# cw312_xc7a35t_fpga_cfg.net
KiCad netlist of a schematic drawn in Altium Designer
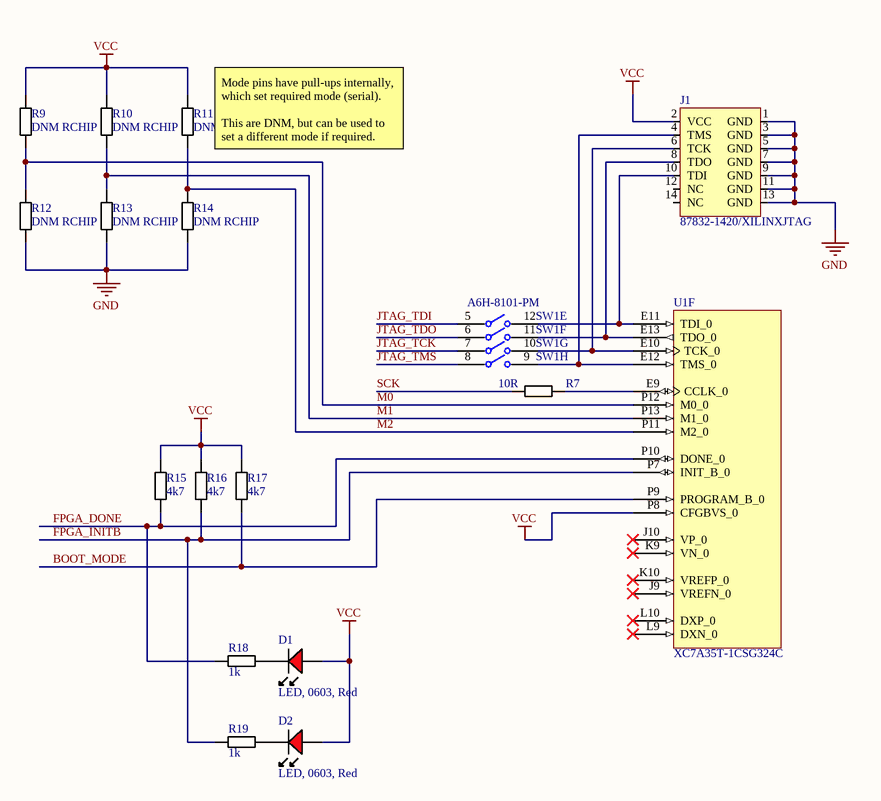
[diagram p0: cw312_xc7a35t_fpga_cfg.SchDoc]

(export (version "E")
  (design (tool "Eeschema 10.0.6"))
  (components
    (comp (ref "D1")
      (value "LED, 0603, Red")
      (footprint "LED-0603-RED")
      (description "Chip LED, Red")
      (fields (field (name "PART NUMBER") "LEDCHIP_0603_RED"))
      (libsource (lib "NewAE_AltiumLib") (part "LED_RED"))
    )
    (comp (ref "D2")
      (value "LED, 0603, Red")
      (footprint "LED-0603-RED")
      (description "Chip LED, Red")
      (fields (field (name "PART NUMBER") "LEDCHIP_0603_RED"))
      (libsource (lib "NewAE_AltiumLib") (part "LED_RED"))
    )
    (comp (ref "J1")
      (value "87832-1420/XILINXJTAG")
      (footprint "87832-1420")
      (description "Molex 14-pin SMD, JTAG Pinout")
      (fields (field (name "MANUFACTURE 1 PART NUMBER") "87832-1420"))
      (libsource (lib "CW1200_MainBoard") (part "87832-1420/XILINXJTAG"))
    )
    (comp (ref "R7")
      (value "10R")
      (footprint "RESC1608X55N")
      (description "10R res, 0603, 1%, 1/10W")
      (fields (field (name "PART NUMBER") "RCHIP-10R-0603") (field (name "TOLERANCE") "1%"))
      (libsource (lib "") (part "RES-EU_1"))
    )
    (comp (ref "R9")
      (value "DNM RCHIP")
      (footprint "RESC1608X55N")
      (description "Do Not Mount Resistor")
      (fields (field (name "PART NUMBER") "RCHIP-DNM-0603"))
      (libsource (lib "") (part "RES-EU_2"))
    )
    (comp (ref "R10")
      (value "DNM RCHIP")
      (footprint "RESC1608X55N")
      (description "Do Not Mount Resistor")
      (fields (field (name "PART NUMBER") "RCHIP-DNM-0603"))
      (libsource (lib "") (part "RES-EU_2"))
    )
    (comp (ref "R11")
      (value "DNM RCHIP")
      (footprint "RESC1608X55N")
      (description "Do Not Mount Resistor")
      (fields (field (name "PART NUMBER") "RCHIP-DNM-0603"))
      (libsource (lib "") (part "RES-EU_2"))
    )
    (comp (ref "R12")
      (value "DNM RCHIP")
      (footprint "RESC1608X55N")
      (description "Do Not Mount Resistor")
      (fields (field (name "PART NUMBER") "RCHIP-DNM-0603"))
      (libsource (lib "") (part "RES-EU_2"))
    )
    (comp (ref "R13")
      (value "DNM RCHIP")
      (footprint "RESC1608X55N")
      (description "Do Not Mount Resistor")
      (fields (field (name "PART NUMBER") "RCHIP-DNM-0603"))
      (libsource (lib "") (part "RES-EU_2"))
    )
    (comp (ref "R14")
      (value "DNM RCHIP")
      (footprint "RESC1608X55N")
      (description "Do Not Mount Resistor")
      (fields (field (name "PART NUMBER") "RCHIP-DNM-0603"))
      (libsource (lib "") (part "RES-EU_2"))
    )
    (comp (ref "R15")
      (value "4k7")
      (footprint "RESC1608X55N")
      (description "4k7 res, 0603, 1%, 1/10W")
      (fields (field (name "PART NUMBER") "RCHIP-4K7-0603") (field (name "TOLERANCE") "1%"))
      (libsource (lib "NewAE_AltiumLib") (part "RES-EU"))
    )
    (comp (ref "R16")
      (value "4k7")
      (footprint "RESC1608X55N")
      (description "4k7 res, 0603, 1%, 1/10W")
      (fields (field (name "PART NUMBER") "RCHIP-4K7-0603") (field (name "TOLERANCE") "1%"))
      (libsource (lib "NewAE_AltiumLib") (part "RES-EU"))
    )
    (comp (ref "R17")
      (value "4k7")
      (footprint "RESC1608X55N")
      (description "4k7 res, 0603, 1%, 1/10W")
      (fields (field (name "PART NUMBER") "RCHIP-4K7-0603") (field (name "TOLERANCE") "1%"))
      (libsource (lib "NewAE_AltiumLib") (part "RES-EU"))
    )
    (comp (ref "R18")
      (value "1k")
      (footprint "RESC1608X55N")
      (description "1k res, 0603, 1%, 1/10W")
      (fields (field (name "PART NUMBER") "RCHIP-1K-0603") (field (name "TOLERANCE") "1%"))
      (libsource (lib "") (part "RES-EU_1"))
    )
    (comp (ref "R19")
      (value "1k")
      (footprint "RESC1608X55N")
      (description "1k res, 0603, 1%, 1/10W")
      (fields (field (name "PART NUMBER") "RCHIP-1K-0603") (field (name "TOLERANCE") "1%"))
      (libsource (lib "") (part "RES-EU_1"))
    )
    (comp (ref "SW1")
      (value "A6H-8101-PM")
      (footprint "FP-A6H-8101-PM-MFG")
      (description "SWITCH SLIDE DIP SPST 25MA 24V")
      (libsource (lib "Altium Content Vault") (part "b1c630a2f26d6f55c46b66680387f8a"))
    )
    (comp (ref "U1")
      (value "XC7A35T-1CSG324C")
      (footprint "CSG324")
      (description "Artix-7 FPGA, 210 User I/Os, 0 GTP, 324-Ball BGA, Speed Grade 1, Commercial Grade, Pb-Free")
      (fields (field (name "MANUFACTURER") "Xilinx"))
      (libsource (lib "Altium Content Vault") (part "XLNX-XC7A35T-CSG324"))
    )
  )
  (nets
    (net (code "1") (name "/BOOT_MODE") (class "Default")
      (node (ref "R17") (pin "2") (pinfunction "2_2") (pintype "passive"))
      (node (ref "U1") (pin "P9") (pinfunction "PROGRAM_B_0_P9") (pintype "input"))
    )
    (net (code "2") (name "/FPGA_DONE") (class "Default")
      (node (ref "R15") (pin "2") (pinfunction "2_2") (pintype "passive"))
      (node (ref "R18") (pin "1") (pinfunction "1_1") (pintype "passive"))
      (node (ref "U1") (pin "P10") (pinfunction "DONE_0_P10") (pintype "bidirectional"))
    )
    (net (code "3") (name "/FPGA_INITB") (class "Default")
      (node (ref "R16") (pin "2") (pinfunction "2_2") (pintype "passive"))
      (node (ref "R19") (pin "1") (pinfunction "1_1") (pintype "passive"))
      (node (ref "U1") (pin "P7") (pinfunction "INIT_B_0_P7") (pintype "bidirectional"))
    )
    (net (code "4") (name "/JTAG_TCK") (class "Default")
      (node (ref "SW1") (pin "7") (pinfunction "7_7") (pintype "passive"))
    )
    (net (code "5") (name "/JTAG_TDI") (class "Default")
      (node (ref "SW1") (pin "5") (pinfunction "5_5") (pintype "passive"))
    )
    (net (code "6") (name "/JTAG_TDO") (class "Default")
      (node (ref "SW1") (pin "6") (pinfunction "6_6") (pintype "passive"))
    )
    (net (code "7") (name "/JTAG_TMS") (class "Default")
      (node (ref "SW1") (pin "8") (pinfunction "8_8") (pintype "passive"))
    )
    (net (code "8") (name "/M0") (class "Default")
      (node (ref "R12") (pin "2") (pinfunction "2_2") (pintype "passive"))
      (node (ref "R9") (pin "1") (pinfunction "1_1") (pintype "passive"))
      (node (ref "U1") (pin "P12") (pinfunction "M0_0_P12") (pintype "input"))
    )
    (net (code "9") (name "/M1") (class "Default")
      (node (ref "R10") (pin "1") (pinfunction "1_1") (pintype "passive"))
      (node (ref "R13") (pin "2") (pinfunction "2_2") (pintype "passive"))
      (node (ref "U1") (pin "P13") (pinfunction "M1_0_P13") (pintype "input"))
    )
    (net (code "10") (name "/M2") (class "Default")
      (node (ref "R11") (pin "1") (pinfunction "1_1") (pintype "passive"))
      (node (ref "R14") (pin "2") (pinfunction "2_2") (pintype "passive"))
      (node (ref "U1") (pin "P11") (pinfunction "M2_0_P11") (pintype "input"))
    )
    (net (code "11") (name "/SCK") (class "Default")
      (node (ref "R7") (pin "1") (pinfunction "1_1") (pintype "passive"))
    )
    (net (code "12") (name "GND") (class "Default")
      (node (ref "J1") (pin "1") (pinfunction "GND_1") (pintype "passive"))
      (node (ref "J1") (pin "11") (pinfunction "GND_11") (pintype "passive"))
      (node (ref "J1") (pin "13") (pinfunction "GND_13") (pintype "passive"))
      (node (ref "J1") (pin "3") (pinfunction "GND_3") (pintype "passive"))
      (node (ref "J1") (pin "5") (pinfunction "GND_5") (pintype "passive"))
      (node (ref "J1") (pin "7") (pinfunction "GND_7") (pintype "passive"))
      (node (ref "J1") (pin "9") (pinfunction "GND_9") (pintype "passive"))
      (node (ref "R12") (pin "1") (pinfunction "1_1") (pintype "passive"))
      (node (ref "R13") (pin "1") (pinfunction "1_1") (pintype "passive"))
      (node (ref "R14") (pin "1") (pinfunction "1_1") (pintype "passive"))
    )
    (net (code "13") (name "Net-(D1-PadK)") (class "Default")
      (node (ref "D1") (pin "K") (pinfunction "K_K") (pintype "passive"))
      (node (ref "R18") (pin "2") (pinfunction "2_2") (pintype "passive"))
    )
    (net (code "14") (name "Net-(D2-PadK)") (class "Default")
      (node (ref "D2") (pin "K") (pinfunction "K_K") (pintype "passive"))
      (node (ref "R19") (pin "2") (pinfunction "2_2") (pintype "passive"))
    )
    (net (code "15") (name "Net-(J1-TCK)") (class "Default")
      (node (ref "J1") (pin "6") (pinfunction "TCK_6") (pintype "passive"))
      (node (ref "SW1") (pin "10") (pinfunction "10_10") (pintype "passive"))
      (node (ref "U1") (pin "E10") (pinfunction "TCK_0_E10") (pintype "input"))
    )
    (net (code "16") (name "Net-(J1-TDI)") (class "Default")
      (node (ref "J1") (pin "10") (pinfunction "TDI_10") (pintype "passive"))
      (node (ref "SW1") (pin "12") (pinfunction "12_12") (pintype "passive"))
      (node (ref "U1") (pin "E11") (pinfunction "TDI_0_E11") (pintype "input"))
    )
    (net (code "17") (name "Net-(J1-TDO)") (class "Default")
      (node (ref "J1") (pin "8") (pinfunction "TDO_8") (pintype "passive"))
      (node (ref "SW1") (pin "11") (pinfunction "11_11") (pintype "passive"))
      (node (ref "U1") (pin "E13") (pinfunction "TDO_0_E13") (pintype "output"))
    )
    (net (code "18") (name "Net-(J1-TMS)") (class "Default")
      (node (ref "J1") (pin "4") (pinfunction "TMS_4") (pintype "passive"))
      (node (ref "SW1") (pin "9") (pinfunction "9_9") (pintype "passive"))
      (node (ref "U1") (pin "E12") (pinfunction "TMS_0_E12") (pintype "input"))
    )
    (net (code "19") (name "Net-(U1F-CCLK_0)") (class "Default")
      (node (ref "R7") (pin "2") (pinfunction "2_2") (pintype "passive"))
      (node (ref "U1") (pin "E9") (pinfunction "CCLK_0_E9") (pintype "bidirectional"))
    )
    (net (code "20") (name "VCC") (class "Default")
      (node (ref "D1") (pin "A") (pinfunction "A_A") (pintype "passive"))
      (node (ref "D2") (pin "A") (pinfunction "A_A") (pintype "passive"))
      (node (ref "J1") (pin "2") (pinfunction "VCC_2") (pintype "passive"))
      (node (ref "R10") (pin "2") (pinfunction "2_2") (pintype "passive"))
      (node (ref "R11") (pin "2") (pinfunction "2_2") (pintype "passive"))
      (node (ref "R15") (pin "1") (pinfunction "1_1") (pintype "passive"))
      (node (ref "R16") (pin "1") (pinfunction "1_1") (pintype "passive"))
      (node (ref "R17") (pin "1") (pinfunction "1_1") (pintype "passive"))
      (node (ref "R9") (pin "2") (pinfunction "2_2") (pintype "passive"))
      (node (ref "U1") (pin "P8") (pinfunction "CFGBVS_0_P8") (pintype "input"))
    )
    (net (code "21") (name "unconnected-(J1-NC-Pad12)") (class "Default")
      (node (ref "J1") (pin "12") (pinfunction "NC_12") (pintype "passive"))
    )
    (net (code "22") (name "unconnected-(J1-NC-Pad14)") (class "Default")
      (node (ref "J1") (pin "14") (pinfunction "NC_14") (pintype "passive"))
    )
    (net (code "23") (name "unconnected-(U1F-DXN_0-PadL9)") (class "Default")
      (node (ref "U1") (pin "L9") (pinfunction "DXN_0_L9") (pintype "input+no_connect"))
    )
    (net (code "24") (name "unconnected-(U1F-DXP_0-PadL10)") (class "Default")
      (node (ref "U1") (pin "L10") (pinfunction "DXP_0_L10") (pintype "input+no_connect"))
    )
    (net (code "25") (name "unconnected-(U1F-VN_0-PadK9)") (class "Default")
      (node (ref "U1") (pin "K9") (pinfunction "VN_0_K9") (pintype "input+no_connect"))
    )
    (net (code "26") (name "unconnected-(U1F-VP_0-PadJ10)") (class "Default")
      (node (ref "U1") (pin "J10") (pinfunction "VP_0_J10") (pintype "input+no_connect"))
    )
    (net (code "27") (name "unconnected-(U1F-VREFN_0-PadJ9)") (class "Default")
      (node (ref "U1") (pin "J9") (pinfunction "VREFN_0_J9") (pintype "input+no_connect"))
    )
    (net (code "28") (name "unconnected-(U1F-VREFP_0-PadK10)") (class "Default")
      (node (ref "U1") (pin "K10") (pinfunction "VREFP_0_K10") (pintype "input+no_connect"))
    )
  )
)
